# Limiter.net
KiCad netlist of a schematic drawn in Altium Designer
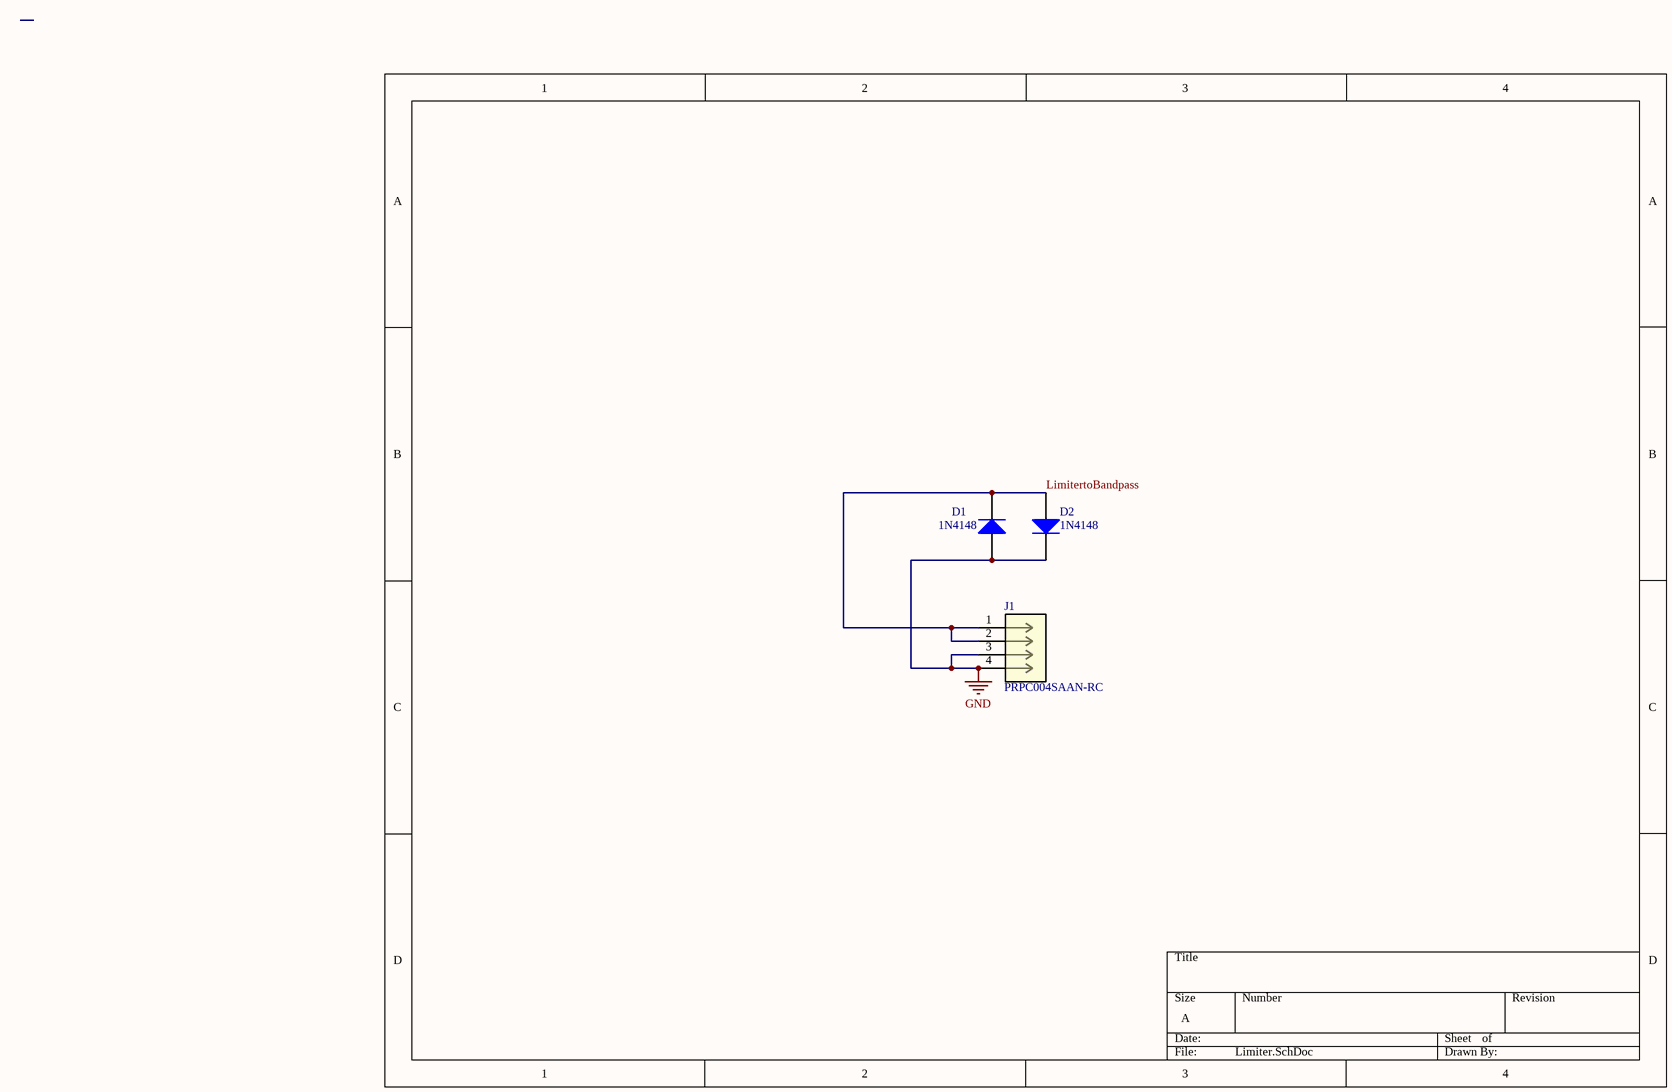
[diagram p0: Limiter.SchDoc]

(export (version "E")
  (design (tool "Eeschema 10.0.6"))
  (components
    (comp (ref "D1")
      (value "1N4148")
      (footprint "NXP-SOD27-2_V")
      (description "High-speed Diode, 100 V, 450 mA, 2-Pin SOD27, RoHS")
      (fields (field (name "MANUFACTURER") "NXP Semiconductors"))
      (libsource (lib "Altium Content Vault") (part "NXP-A1K2-2"))
    )
    (comp (ref "D2")
      (value "1N4148")
      (footprint "NXP-SOD27-2_V")
      (description "High-speed Diode, 100 V, 450 mA, 2-Pin SOD27, RoHS")
      (fields (field (name "MANUFACTURER") "NXP Semiconductors"))
      (libsource (lib "Altium Content Vault") (part "NXP-A1K2-2"))
    )
    (comp (ref "J1")
      (value "PRPC004SAAN-RC")
      (footprint "CONN4_PRPC004_SUL")
      (description "No Description Available")
      (libsource (lib "PRPC004SAAN-RC") (part "PRPC004SAAN-RC"))
    )
  )
  (nets
    (net (code "1") (name "/LimitertoBandpass") (class "Default")
      (node (ref "D1") (pin "2") (pinfunction "K_2") (pintype "passive"))
      (node (ref "D2") (pin "1") (pinfunction "A_1") (pintype "passive"))
      (node (ref "J1") (pin "1") (pinfunction "1_1") (pintype "passive"))
      (node (ref "J1") (pin "2") (pinfunction "2_2") (pintype "passive"))
    )
    (net (code "2") (name "GND") (class "Default")
      (node (ref "D1") (pin "1") (pinfunction "A_1") (pintype "passive"))
      (node (ref "D2") (pin "2") (pinfunction "K_2") (pintype "passive"))
      (node (ref "J1") (pin "3") (pinfunction "3_3") (pintype "passive"))
      (node (ref "J1") (pin "4") (pinfunction "4_4") (pintype "passive"))
    )
  )
)
